# PIC32MM-Breakout.net
KiCad netlist of a schematic drawn in Altium Designer
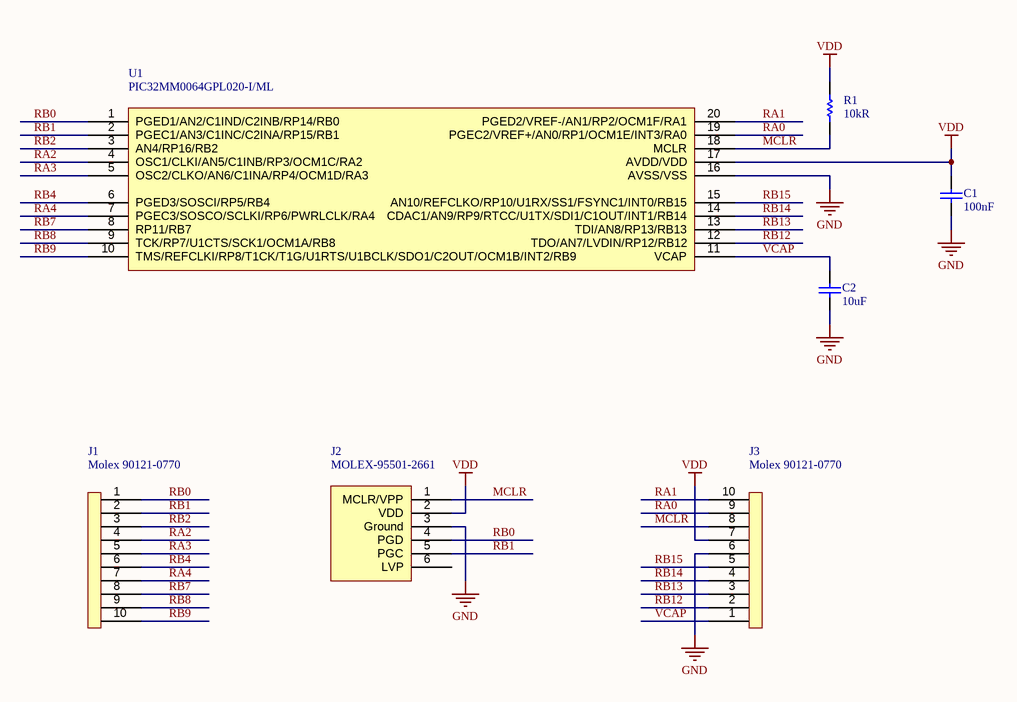
[diagram p0: PIC32MM-Breakout.SchDoc]

(export (version "E")
  (design (tool "Eeschema 10.0.6"))
  (components
    (comp (ref "C1") (value "100nF") (footprint "Capacitor 0603") (libsource (lib "x-io") (part "Capacitor")))
    (comp (ref "C2") (value "10uF") (footprint "Capacitor 0603") (libsource (lib "x-io") (part "Capacitor")))
    (comp (ref "J1")
      (value "Molex 90121-0770")
      (footprint "Molex 90121-0770")
      (libsource (lib "") (part "Molex 90121-0770_1"))
    )
    (comp (ref "J2")
      (value "MOLEX-95501-2661")
      (footprint "Molex 90120-0926")
      (libsource (lib "x-io") (part "MPLAB ICSP"))
    )
    (comp (ref "J3")
      (value "Molex 90121-0770")
      (footprint "Molex 90121-0770")
      (libsource (lib "x-io") (part "Molex 90121-0770"))
    )
    (comp (ref "R1") (value "10kR") (footprint "Resistor 0603") (libsource (lib "x-io") (part "Resistor")))
    (comp (ref "U1")
      (value "PIC32MM0064GPL020-I/ML")
      (footprint "QFN-20")
      (libsource (lib "x-io") (part "PIC32MM0064GPL020-I/ML"))
    )
  )
  (nets
    (net (code "1") (name "/MCLR") (class "Default")
      (node (ref "J2") (pin "1") (pinfunction "MCLR/VPP_1") (pintype "passive"))
      (node (ref "J3") (pin "8") (pinfunction "8_8") (pintype "passive"))
      (node (ref "R1") (pin "1") (pinfunction "1_1") (pintype "passive"))
      (node (ref "U1") (pin "18") (pinfunction "MCLR_18") (pintype "passive"))
    )
    (net (code "2") (name "/RA0") (class "Default")
      (node (ref "J3") (pin "9") (pinfunction "9_9") (pintype "passive"))
      (node (ref "U1") (pin "19") (pinfunction "PGEC2/VREF+/AN0/RP1/OCM1E/INT3/RA0_19") (pintype "passive"))
    )
    (net (code "3") (name "/RA1") (class "Default")
      (node (ref "J3") (pin "10") (pinfunction "10_10") (pintype "passive"))
      (node (ref "U1") (pin "20") (pinfunction "PGED2/VREF-/AN1/RP2/OCM1F/RA1_20") (pintype "passive"))
    )
    (net (code "4") (name "/RA2") (class "Default")
      (node (ref "J1") (pin "4") (pinfunction "4_4") (pintype "passive"))
      (node (ref "U1") (pin "4") (pinfunction "OSC1/CLKI/AN5/C1INB/RP3/OCM1C/RA2_4") (pintype "passive"))
    )
    (net (code "5") (name "/RA3") (class "Default")
      (node (ref "J1") (pin "5") (pinfunction "5_5") (pintype "passive"))
      (node (ref "U1") (pin "5") (pinfunction "OSC2/CLKO/AN6/C1INA/RP4/OCM1D/RA3_5") (pintype "passive"))
    )
    (net (code "6") (name "/RA4") (class "Default")
      (node (ref "J1") (pin "7") (pinfunction "7_7") (pintype "passive"))
      (node (ref "U1") (pin "7") (pinfunction "PGEC3/SOSCO/SCLKI/RP6/PWRLCLK/RA4_7") (pintype "passive"))
    )
    (net (code "7") (name "/RB0") (class "Default")
      (node (ref "J1") (pin "1") (pinfunction "1_1") (pintype "passive"))
      (node (ref "J2") (pin "4") (pinfunction "PGD_4") (pintype "passive"))
      (node (ref "U1") (pin "1") (pinfunction "PGED1/AN2/C1IND/C2INB/RP14/RB0_1") (pintype "passive"))
    )
    (net (code "8") (name "/RB1") (class "Default")
      (node (ref "J1") (pin "2") (pinfunction "2_2") (pintype "passive"))
      (node (ref "J2") (pin "5") (pinfunction "PGC_5") (pintype "passive"))
      (node (ref "U1") (pin "2") (pinfunction "PGEC1/AN3/C1INC/C2INA/RP15/RB1_2") (pintype "passive"))
    )
    (net (code "9") (name "/RB2") (class "Default")
      (node (ref "J1") (pin "3") (pinfunction "3_3") (pintype "passive"))
      (node (ref "U1") (pin "3") (pinfunction "AN4/RP16/RB2_3") (pintype "passive"))
    )
    (net (code "10") (name "/RB4") (class "Default")
      (node (ref "J1") (pin "6") (pinfunction "6_6") (pintype "passive"))
      (node (ref "U1") (pin "6") (pinfunction "PGED3/SOSCI/RP5/RB4_6") (pintype "passive"))
    )
    (net (code "11") (name "/RB7") (class "Default")
      (node (ref "J1") (pin "8") (pinfunction "8_8") (pintype "passive"))
      (node (ref "U1") (pin "8") (pinfunction "RP11/RB7_8") (pintype "passive"))
    )
    (net (code "12") (name "/RB8") (class "Default")
      (node (ref "J1") (pin "9") (pinfunction "9_9") (pintype "passive"))
      (node (ref "U1") (pin "9") (pinfunction "TCK/RP7/U1CTS/SCK1/OCM1A/RB8_9") (pintype "passive"))
    )
    (net (code "13") (name "/RB9") (class "Default")
      (node (ref "J1") (pin "10") (pinfunction "10_10") (pintype "passive"))
      (node (ref "U1") (pin "10") (pinfunction "TMS/REFCLKI/RP8/T1CK/T1G/U1RTS/U1BCLK/SDO1/C2OUT/OCM1B/INT2/RB9_10") (pintype "passive"))
    )
    (net (code "14") (name "/RB12") (class "Default")
      (node (ref "J3") (pin "2") (pinfunction "2_2") (pintype "passive"))
      (node (ref "U1") (pin "12") (pinfunction "TDO/AN7/LVDIN/RP12/RB12_12") (pintype "passive"))
    )
    (net (code "15") (name "/RB13") (class "Default")
      (node (ref "J3") (pin "3") (pinfunction "3_3") (pintype "passive"))
      (node (ref "U1") (pin "13") (pinfunction "TDI/AN8/RP13/RB13_13") (pintype "passive"))
    )
    (net (code "16") (name "/RB14") (class "Default")
      (node (ref "J3") (pin "4") (pinfunction "4_4") (pintype "passive"))
      (node (ref "U1") (pin "14") (pinfunction "CDAC1/AN9/RP9/RTCC/U1TX/SDI1/C1OUT/INT1/RB14_14") (pintype "passive"))
    )
    (net (code "17") (name "/RB15") (class "Default")
      (node (ref "J3") (pin "5") (pinfunction "5_5") (pintype "passive"))
      (node (ref "U1") (pin "15") (pinfunction "AN10/REFCLKO/RP10/U1RX/SS1/FSYNC1/INT0/RB15_15") (pintype "passive"))
    )
    (net (code "18") (name "/VCAP") (class "Default")
      (node (ref "C2") (pin "2") (pinfunction "2_2") (pintype "passive"))
      (node (ref "J3") (pin "1") (pinfunction "1_1") (pintype "passive"))
      (node (ref "U1") (pin "11") (pinfunction "VCAP_11") (pintype "passive"))
    )
    (net (code "19") (name "GND") (class "Default")
      (node (ref "C1") (pin "1") (pinfunction "1_1") (pintype "passive"))
      (node (ref "C2") (pin "1") (pinfunction "1_1") (pintype "passive"))
      (node (ref "J2") (pin "3") (pinfunction "Ground_3") (pintype "passive"))
      (node (ref "J3") (pin "6") (pinfunction "6_6") (pintype "passive"))
      (node (ref "U1") (pin "16") (pinfunction "AVSS/VSS_16") (pintype "passive"))
    )
    (net (code "20") (name "VDD") (class "Default")
      (node (ref "C1") (pin "2") (pinfunction "2_2") (pintype "passive"))
      (node (ref "J2") (pin "2") (pinfunction "VDD_2") (pintype "passive"))
      (node (ref "J3") (pin "7") (pinfunction "7_7") (pintype "passive"))
      (node (ref "R1") (pin "2") (pinfunction "2_2") (pintype "passive"))
      (node (ref "U1") (pin "17") (pinfunction "AVDD/VDD_17") (pintype "passive"))
    )
    (net (code "21") (name "unconnected-(J2-LVP-Pad6)") (class "Default")
      (node (ref "J2") (pin "6") (pinfunction "LVP_6") (pintype "passive"))
    )
  )
)
